# filter-2.net
KiCad netlist of a schematic drawn in Altium Designer
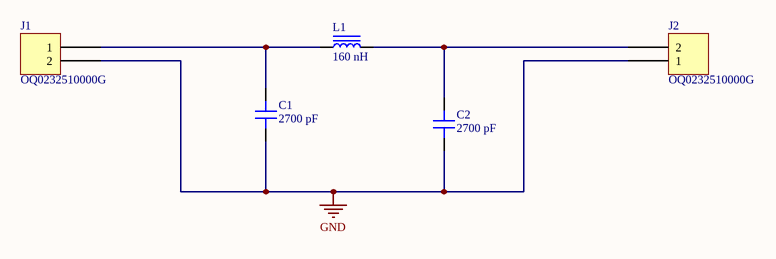
[diagram p0: filter-2.SchDoc]

(export (version "E")
  (design (tool "Eeschema 10.0.6"))
  (components
    (comp (ref "C1")
      (value "2700 pF")
      (footprint "CAP 0603_1608")
      (description "CAP CER 2700PF 25V NP0 0603")
      (fields (field (name "PART NUMBER") "C0603C272F3GAC7867") (field (name "MANUFACTURER") "KEMET"))
      (libsource (lib "Celestial Altium Library - altium_library") (part "Capacitor"))
    )
    (comp (ref "C2")
      (value "2700 pF")
      (footprint "CAP 0603_1608")
      (description "CAP CER 2700PF 25V NP0 0603")
      (fields (field (name "PART NUMBER") "C0603C272F3GAC7867") (field (name "MANUFACTURER") "KEMET"))
      (libsource (lib "Celestial Altium Library - altium_library") (part "Capacitor"))
    )
    (comp (ref "J1")
      (value "OQ0232510000G")
      (footprint "FCI 06-381-2PIN")
      (description "TERM BLOCK HDR 2POS 90DEG 3.81MM")
      (fields (field (name "MANUFACTURER") "Amphenol Anytek"))
      (libsource (lib "Celestial Altium Library - altium_library") (part "2 Pin"))
    )
    (comp (ref "J2")
      (value "OQ0232510000G")
      (footprint "FCI 06-381-2PIN")
      (description "TERM BLOCK HDR 2POS 90DEG 3.81MM")
      (fields (field (name "MANUFACTURER") "Amphenol Anytek"))
      (libsource (lib "") (part "2 Pin_1"))
    )
    (comp (ref "L1")
      (value "160 nH")
      (footprint "IND 0402_1005 RF WW")
      (description "FIXED IND 160NH 480MA 330MOHM SM")
      (fields
        (field (name "PART NUMBER") "LQW15CNR16J00D")
        (field (name "MANUFACTURER") "Murata Electronics")
      )
      (libsource (lib "Celestial Altium Library - altium_library") (part "Inductor"))
    )
  )
  (nets
    (net (code "1") (name "GND") (class "Default")
      (node (ref "C1") (pin "1") (pinfunction "1_1") (pintype "passive"))
      (node (ref "C2") (pin "1") (pinfunction "1_1") (pintype "passive"))
      (node (ref "J1") (pin "2") (pinfunction "2_2") (pintype "passive"))
      (node (ref "J2") (pin "1") (pinfunction "1_1") (pintype "passive"))
    )
    (net (code "2") (name "Net-(C1-Pad2)") (class "Default")
      (node (ref "C1") (pin "2") (pinfunction "2_2") (pintype "passive"))
      (node (ref "J1") (pin "1") (pinfunction "1_1") (pintype "passive"))
      (node (ref "L1") (pin "1") (pinfunction "1_1") (pintype "passive"))
    )
    (net (code "3") (name "Net-(C2-Pad2)") (class "Default")
      (node (ref "C2") (pin "2") (pinfunction "2_2") (pintype "passive"))
      (node (ref "J2") (pin "2") (pinfunction "2_2") (pintype "passive"))
      (node (ref "L1") (pin "2") (pinfunction "2_2") (pintype "passive"))
    )
  )
)
